# 1_Measurement_and_MPPT.net
KiCad netlist of a schematic drawn in Altium Designer
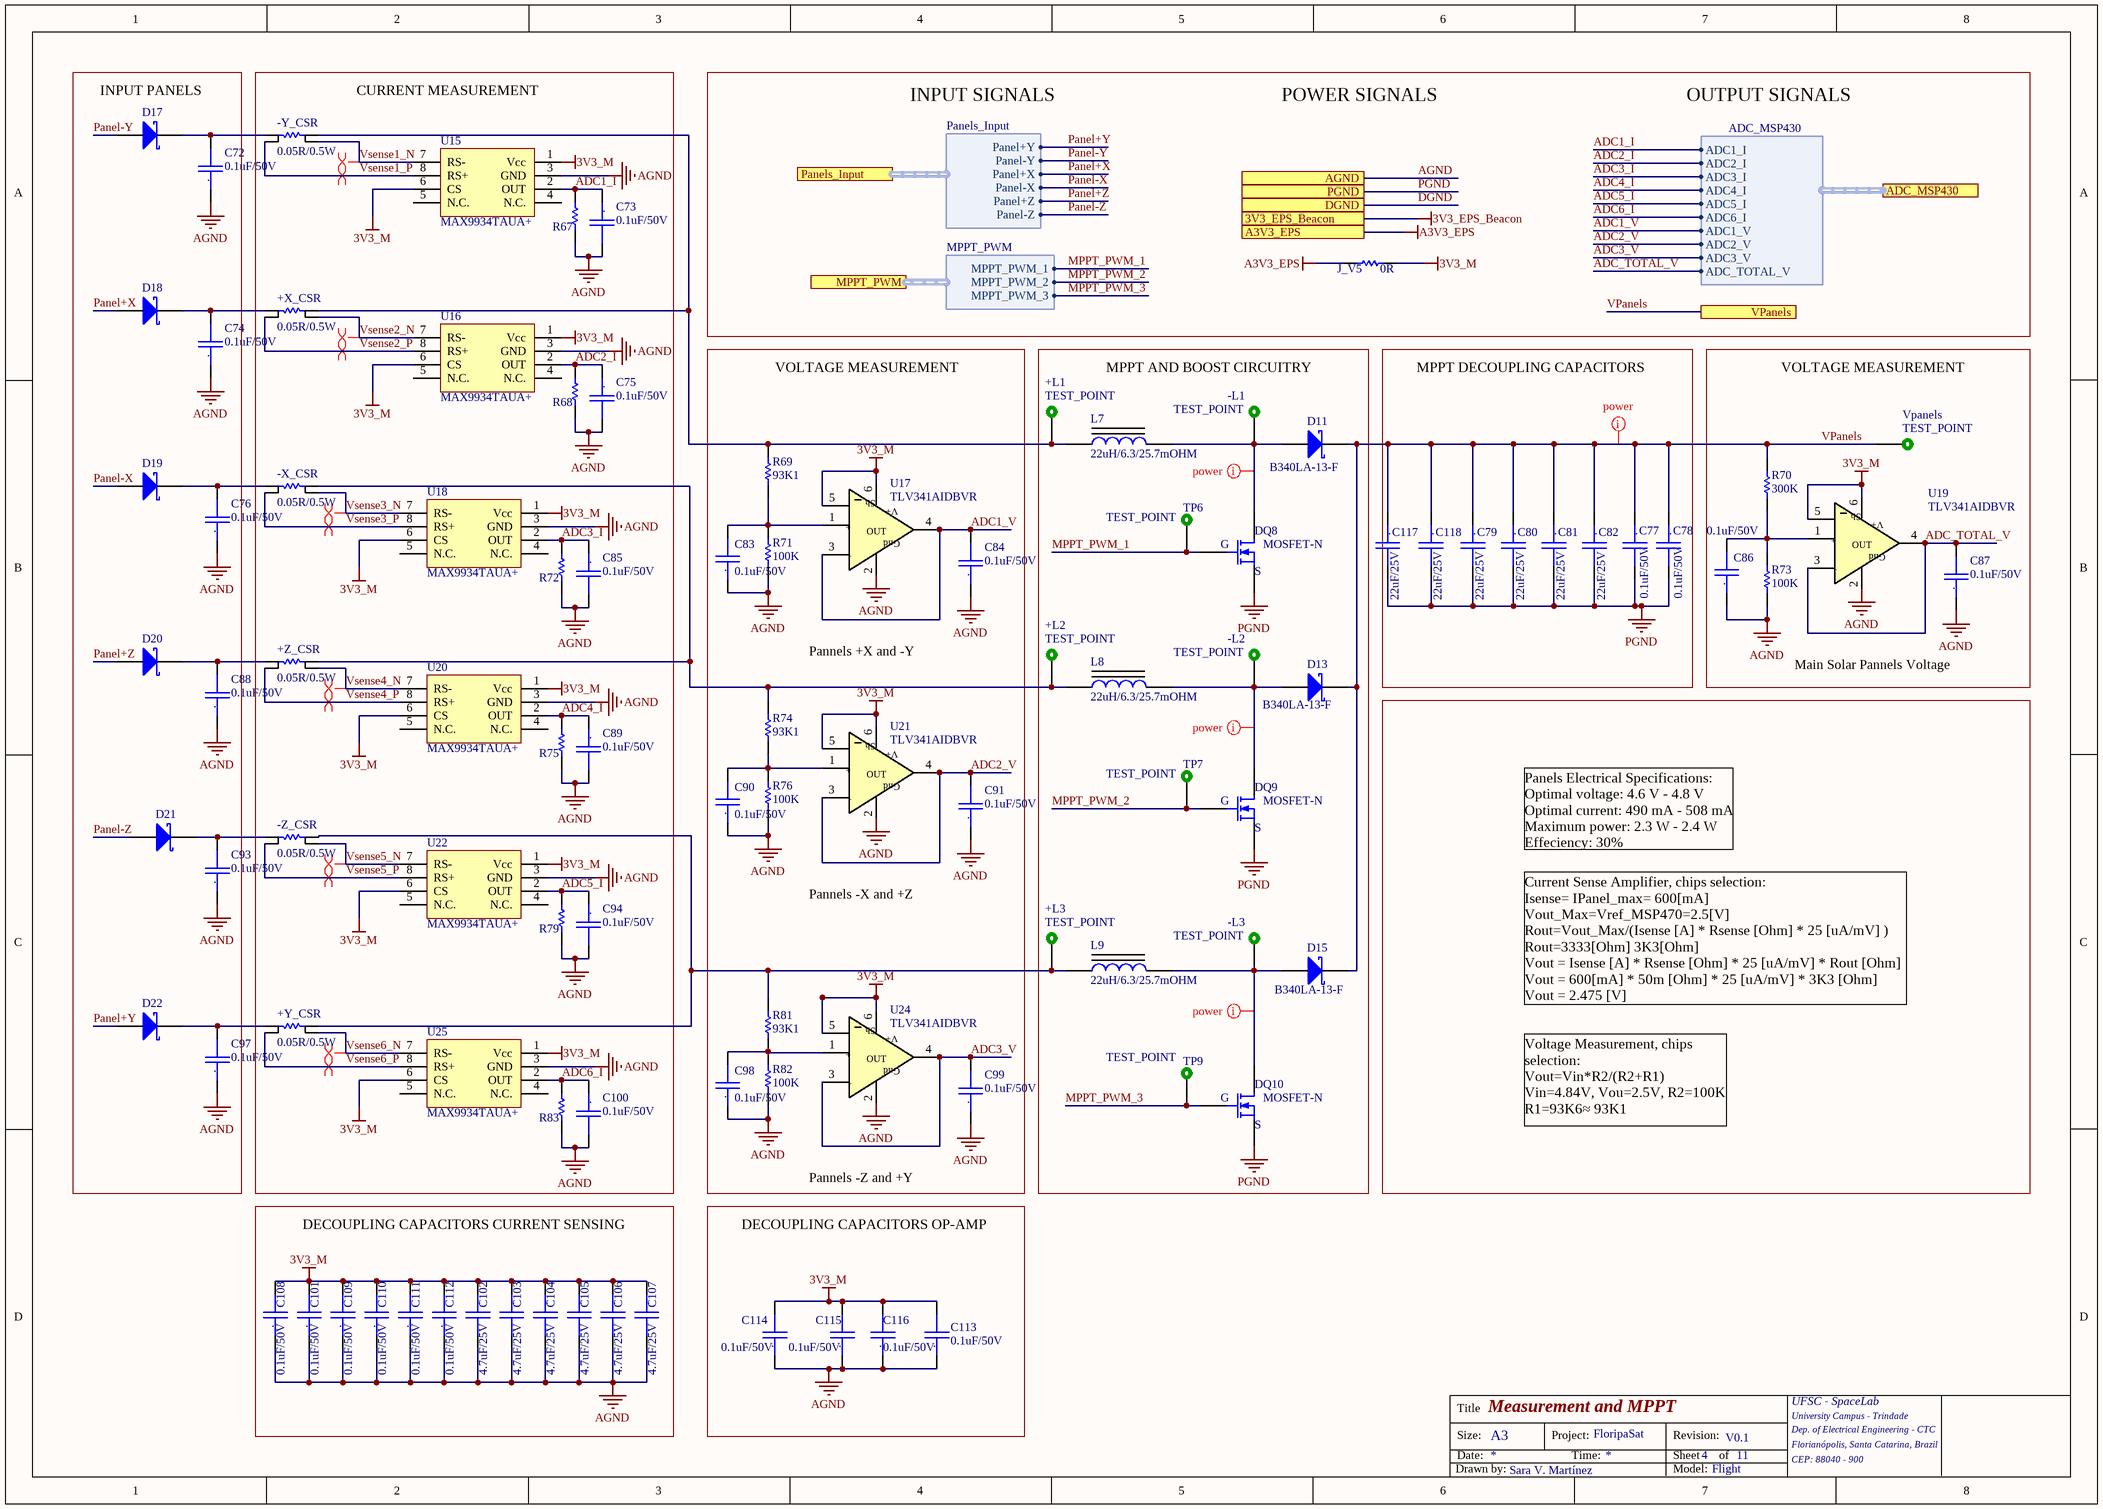
[diagram p0: 1_Measurement_and_MPPT.SchDoc]

(export (version "E")
  (design (tool "Eeschema 10.0.6"))
  (components
    (comp (ref "+L1")
      (value "TEST_POINT")
      (footprint "TEST_POINT")
      (description "Test point")
      (libsource (lib "PCB_Project_FlightModel_EPS") (part "TEST_POINT"))
    )
    (comp (ref "+L2")
      (value "TEST_POINT")
      (footprint "TEST_POINT")
      (description "Test point")
      (libsource (lib "PCB_Project_FlightModel_EPS") (part "TEST_POINT"))
    )
    (comp (ref "+L3")
      (value "TEST_POINT")
      (footprint "TEST_POINT")
      (description "Test point")
      (libsource (lib "PCB_Project_FlightModel_EPS") (part "TEST_POINT"))
    )
    (comp (ref "+X_CSR")
      (value "0.05R/0.5W")
      (footprint "1206 - ohmite")
      (description "Current Sense Resistors - SMD 0.05ohm .5% 4 Terminal")
      (fields (field (name "PARTNUMBER") "LVK12R050DER") (field (name "MANUFACTURER") "Ohmite"))
      (libsource (lib "PCB_Project_FlightModel_EPS") (part "R0.05R_0.5%_0.5W_1206"))
    )
    (comp (ref "+Y_CSR")
      (value "0.05R/0.5W")
      (footprint "1206 - ohmite")
      (description "Current Sense Resistors - SMD 0.05ohm .5% 4 Terminal")
      (fields (field (name "PARTNUMBER") "LVK12R050DER") (field (name "MANUFACTURER") "Ohmite"))
      (libsource (lib "PCB_Project_FlightModel_EPS") (part "R0.05R_0.5%_0.5W_1206"))
    )
    (comp (ref "+Z_CSR")
      (value "0.05R/0.5W")
      (footprint "1206 - ohmite")
      (description "Current Sense Resistors - SMD 0.05ohm .5% 4 Terminal")
      (fields (field (name "PARTNUMBER") "LVK12R050DER") (field (name "MANUFACTURER") "Ohmite"))
      (libsource (lib "PCB_Project_FlightModel_EPS") (part "R0.05R_0.5%_0.5W_1206"))
    )
    (comp (ref "-L1")
      (value "TEST_POINT")
      (footprint "TEST_POINT")
      (description "Test point")
      (libsource (lib "PCB_Project_FlightModel_EPS") (part "TEST_POINT"))
    )
    (comp (ref "-L2")
      (value "TEST_POINT")
      (footprint "TEST_POINT")
      (description "Test point")
      (libsource (lib "PCB_Project_FlightModel_EPS") (part "TEST_POINT"))
    )
    (comp (ref "-L3")
      (value "TEST_POINT")
      (footprint "TEST_POINT")
      (description "Test point")
      (libsource (lib "PCB_Project_FlightModel_EPS") (part "TEST_POINT"))
    )
    (comp (ref "-X_CSR")
      (value "0.05R/0.5W")
      (footprint "1206 - ohmite")
      (description "Current Sense Resistors - SMD 0.05ohm .5% 4 Terminal")
      (fields (field (name "PARTNUMBER") "LVK12R050DER") (field (name "MANUFACTURER") "Ohmite"))
      (libsource (lib "PCB_Project_FlightModel_EPS") (part "R0.05R_0.5%_0.5W_1206"))
    )
    (comp (ref "-Y_CSR")
      (value "0.05R/0.5W")
      (footprint "1206 - ohmite")
      (description "Current Sense Resistors - SMD 0.05ohm .5% 4 Terminal")
      (fields (field (name "PARTNUMBER") "LVK12R050DER") (field (name "MANUFACTURER") "Ohmite"))
      (libsource (lib "PCB_Project_FlightModel_EPS") (part "R0.05R_0.5%_0.5W_1206"))
    )
    (comp (ref "-Z_CSR")
      (value "0.05R/0.5W")
      (footprint "1206 - ohmite")
      (description "Current Sense Resistors - SMD 0.05ohm .5% 4 Terminal")
      (fields (field (name "PARTNUMBER") "LVK12R050DER") (field (name "MANUFACTURER") "Ohmite"))
      (libsource (lib "PCB_Project_FlightModel_EPS") (part "R0.05R_0.5%_0.5W_1206"))
    )
    (comp (ref "C72")
      (value "0.1uF/50V")
      (footprint "CC0603")
      (description "CAP CER 0.1UF 50V 10% X7R 0603")
      (fields (field (name "PARTNUMBER") "CC0603KPX7R9BB104") (field (name "MANUFACTURER") "Yageo"))
      (libsource (lib "PCB_Project_FlightModel_EPS") (part "Cap_Cer_X7R_0.1uF_50V_0603"))
    )
    (comp (ref "C73")
      (value "0.1uF/50V")
      (footprint "CC0603")
      (description "CAP CER 0.1UF 50V 10% X7R 0603")
      (fields (field (name "PARTNUMBER") "CC0603KPX7R9BB104") (field (name "MANUFACTURER") "Yageo"))
      (libsource (lib "PCB_Project_FlightModel_EPS") (part "Cap_Cer_X7R_0.1uF_50V_0603"))
    )
    (comp (ref "C74")
      (value "0.1uF/50V")
      (footprint "CC0603")
      (description "CAP CER 0.1UF 50V 10% X7R 0603")
      (fields (field (name "PARTNUMBER") "CC0603KPX7R9BB104") (field (name "MANUFACTURER") "Yageo"))
      (libsource (lib "PCB_Project_FlightModel_EPS") (part "Cap_Cer_X7R_0.1uF_50V_0603"))
    )
    (comp (ref "C75")
      (value "0.1uF/50V")
      (footprint "CC0603")
      (description "CAP CER 0.1UF 50V 10% X7R 0603")
      (fields (field (name "PARTNUMBER") "CC0603KPX7R9BB104") (field (name "MANUFACTURER") "Yageo"))
      (libsource (lib "PCB_Project_FlightModel_EPS") (part "Cap_Cer_X7R_0.1uF_50V_0603"))
    )
    (comp (ref "C76")
      (value "0.1uF/50V")
      (footprint "CC0603")
      (description "CAP CER 0.1UF 50V 10% X7R 0603")
      (fields (field (name "PARTNUMBER") "CC0603KPX7R9BB104") (field (name "MANUFACTURER") "Yageo"))
      (libsource (lib "PCB_Project_FlightModel_EPS") (part "Cap_Cer_X7R_0.1uF_50V_0603"))
    )
    (comp (ref "C77")
      (value "0.1uF/50V")
      (footprint "CC0805")
      (description "CAP CER 0.1UF 50V 10% X7R 0805")
      (fields (field (name "PARTNUMBER") "CC0805KRX7R9BB104") (field (name "MANUFACTURER") "Yageo"))
      (libsource (lib "PCB_Project_FlightModel_EPS") (part "Cap_Cer_X7R_0.1uF_50V_0805"))
    )
    (comp (ref "C78")
      (value "0.1uF/50V")
      (footprint "CC0805")
      (description "CAP CER 0.1UF 50V 10% X7R 0805")
      (fields (field (name "PARTNUMBER") "CC0805KRX7R9BB104") (field (name "MANUFACTURER") "Yageo"))
      (libsource (lib "PCB_Project_FlightModel_EPS") (part "Cap_Cer_X7R_0.1uF_50V_0805"))
    )
    (comp (ref "C79")
      (value "22uF/25V")
      (footprint "CC1210")
      (description "CAP CER 22uF 25V 10% X7R 1210")
      (fields (field (name "PARTNUMBER") "GRM32ER71E226KE15L") (field (name "MANUFACTURER") "Murata"))
      (libsource (lib "PCB_Project_FlightModel_EPS") (part "Cap_Cer_X7R_22uF_25V_1210"))
    )
    (comp (ref "C80")
      (value "22uF/25V")
      (footprint "CC1210")
      (description "CAP CER 22uF 25V 10% X7R 1210")
      (fields (field (name "PARTNUMBER") "GRM32ER71E226KE15L") (field (name "MANUFACTURER") "Murata"))
      (libsource (lib "PCB_Project_FlightModel_EPS") (part "Cap_Cer_X7R_22uF_25V_1210"))
    )
    (comp (ref "C81")
      (value "22uF/25V")
      (footprint "CC1210")
      (description "CAP CER 22uF 25V 10% X7R 1210")
      (fields (field (name "PARTNUMBER") "GRM32ER71E226KE15L") (field (name "MANUFACTURER") "Murata"))
      (libsource (lib "PCB_Project_FlightModel_EPS") (part "Cap_Cer_X7R_22uF_25V_1210"))
    )
    (comp (ref "C82")
      (value "22uF/25V")
      (footprint "CC1210")
      (description "CAP CER 22uF 25V 10% X7R 1210")
      (fields (field (name "PARTNUMBER") "GRM32ER71E226KE15L") (field (name "MANUFACTURER") "Murata"))
      (libsource (lib "PCB_Project_FlightModel_EPS") (part "Cap_Cer_X7R_22uF_25V_1210"))
    )
    (comp (ref "C83")
      (value "0.1uF/50V")
      (footprint "CC0603")
      (description "CAP CER 0.1UF 50V 10% X7R 0603")
      (fields (field (name "PARTNUMBER") "CC0603KPX7R9BB104") (field (name "MANUFACTURER") "Yageo"))
      (libsource (lib "PCB_Project_FlightModel_EPS") (part "Cap_Cer_X7R_0.1uF_50V_0603"))
    )
    (comp (ref "C84")
      (value "0.1uF/50V")
      (footprint "CC0603")
      (description "CAP CER 0.1UF 50V 10% X7R 0603")
      (fields (field (name "PARTNUMBER") "CC0603KPX7R9BB104") (field (name "MANUFACTURER") "Yageo"))
      (libsource (lib "PCB_Project_FlightModel_EPS") (part "Cap_Cer_X7R_0.1uF_50V_0603"))
    )
    (comp (ref "C85")
      (value "0.1uF/50V")
      (footprint "CC0603")
      (description "CAP CER 0.1UF 50V 10% X7R 0603")
      (fields (field (name "PARTNUMBER") "CC0603KPX7R9BB104") (field (name "MANUFACTURER") "Yageo"))
      (libsource (lib "PCB_Project_FlightModel_EPS") (part "Cap_Cer_X7R_0.1uF_50V_0603"))
    )
    (comp (ref "C86")
      (value "0.1uF/50V")
      (footprint "CC0603")
      (description "CAP CER 0.1UF 50V 10% X7R 0603")
      (fields (field (name "PARTNUMBER") "CC0603KPX7R9BB104") (field (name "MANUFACTURER") "Yageo"))
      (libsource (lib "PCB_Project_FlightModel_EPS") (part "Cap_Cer_X7R_0.1uF_50V_0603"))
    )
    (comp (ref "C87")
      (value "0.1uF/50V")
      (footprint "CC0603")
      (description "CAP CER 0.1UF 50V 10% X7R 0603")
      (fields (field (name "PARTNUMBER") "CC0603KPX7R9BB104") (field (name "MANUFACTURER") "Yageo"))
      (libsource (lib "PCB_Project_FlightModel_EPS") (part "Cap_Cer_X7R_0.1uF_50V_0603"))
    )
    (comp (ref "C88")
      (value "0.1uF/50V")
      (footprint "CC0603")
      (description "CAP CER 0.1UF 50V 10% X7R 0603")
      (fields (field (name "PARTNUMBER") "CC0603KPX7R9BB104") (field (name "MANUFACTURER") "Yageo"))
      (libsource (lib "PCB_Project_FlightModel_EPS") (part "Cap_Cer_X7R_0.1uF_50V_0603"))
    )
    (comp (ref "C89")
      (value "0.1uF/50V")
      (footprint "CC0603")
      (description "CAP CER 0.1UF 50V 10% X7R 0603")
      (fields (field (name "PARTNUMBER") "CC0603KPX7R9BB104") (field (name "MANUFACTURER") "Yageo"))
      (libsource (lib "PCB_Project_FlightModel_EPS") (part "Cap_Cer_X7R_0.1uF_50V_0603"))
    )
    (comp (ref "C90")
      (value "0.1uF/50V")
      (footprint "CC0603")
      (description "CAP CER 0.1UF 50V 10% X7R 0603")
      (fields (field (name "PARTNUMBER") "CC0603KPX7R9BB104") (field (name "MANUFACTURER") "Yageo"))
      (libsource (lib "PCB_Project_FlightModel_EPS") (part "Cap_Cer_X7R_0.1uF_50V_0603"))
    )
    (comp (ref "C91")
      (value "0.1uF/50V")
      (footprint "CC0603")
      (description "CAP CER 0.1UF 50V 10% X7R 0603")
      (fields (field (name "PARTNUMBER") "CC0603KPX7R9BB104") (field (name "MANUFACTURER") "Yageo"))
      (libsource (lib "PCB_Project_FlightModel_EPS") (part "Cap_Cer_X7R_0.1uF_50V_0603"))
    )
    (comp (ref "C93")
      (value "0.1uF/50V")
      (footprint "CC0603")
      (description "CAP CER 0.1UF 50V 10% X7R 0603")
      (fields (field (name "PARTNUMBER") "CC0603KPX7R9BB104") (field (name "MANUFACTURER") "Yageo"))
      (libsource (lib "PCB_Project_FlightModel_EPS") (part "Cap_Cer_X7R_0.1uF_50V_0603"))
    )
    (comp (ref "C94")
      (value "0.1uF/50V")
      (footprint "CC0603")
      (description "CAP CER 0.1UF 50V 10% X7R 0603")
      (fields (field (name "PARTNUMBER") "CC0603KPX7R9BB104") (field (name "MANUFACTURER") "Yageo"))
      (libsource (lib "PCB_Project_FlightModel_EPS") (part "Cap_Cer_X7R_0.1uF_50V_0603"))
    )
    (comp (ref "C97")
      (value "0.1uF/50V")
      (footprint "CC0603")
      (description "CAP CER 0.1UF 50V 10% X7R 0603")
      (fields (field (name "PARTNUMBER") "CC0603KPX7R9BB104") (field (name "MANUFACTURER") "Yageo"))
      (libsource (lib "PCB_Project_FlightModel_EPS") (part "Cap_Cer_X7R_0.1uF_50V_0603"))
    )
    (comp (ref "C98")
      (value "0.1uF/50V")
      (footprint "CC0603")
      (description "CAP CER 0.1UF 50V 10% X7R 0603")
      (fields (field (name "PARTNUMBER") "CC0603KPX7R9BB104") (field (name "MANUFACTURER") "Yageo"))
      (libsource (lib "PCB_Project_FlightModel_EPS") (part "Cap_Cer_X7R_0.1uF_50V_0603"))
    )
    (comp (ref "C99")
      (value "0.1uF/50V")
      (footprint "CC0603")
      (description "CAP CER 0.1UF 50V 10% X7R 0603")
      (fields (field (name "PARTNUMBER") "CC0603KPX7R9BB104") (field (name "MANUFACTURER") "Yageo"))
      (libsource (lib "PCB_Project_FlightModel_EPS") (part "Cap_Cer_X7R_0.1uF_50V_0603"))
    )
    (comp (ref "C100")
      (value "0.1uF/50V")
      (footprint "CC0603")
      (description "CAP CER 0.1UF 50V 10% X7R 0603")
      (fields (field (name "PARTNUMBER") "CC0603KPX7R9BB104") (field (name "MANUFACTURER") "Yageo"))
      (libsource (lib "PCB_Project_FlightModel_EPS") (part "Cap_Cer_X7R_0.1uF_50V_0603"))
    )
    (comp (ref "C101")
      (value "0.1uF/50V")
      (footprint "CC0603")
      (description "CAP CER 0.1UF 50V 10% X7R 0603")
      (fields (field (name "PARTNUMBER") "CC0603KPX7R9BB104") (field (name "MANUFACTURER") "Yageo"))
      (libsource (lib "PCB_Project_FlightModel_EPS") (part "Cap_Cer_X7R_0.1uF_50V_0603"))
    )
    (comp (ref "C102")
      (value "4.7uF/25V")
      (footprint "CC0805")
      (description "CAP CER 4.7uF 25V 10% X7R 0805")
      (fields (field (name "PARTNUMBER") "CC0805KKX7R8BB475") (field (name "MANUFACTURER") "Yageo"))
      (libsource (lib "PCB_Project_FlightModel_EPS") (part "Cap_Cer_X7R_4.7uF_25V_0805"))
    )
    (comp (ref "C103")
      (value "4.7uF/25V")
      (footprint "CC0805")
      (description "CAP CER 4.7uF 25V 10% X7R 0805")
      (fields (field (name "PARTNUMBER") "CC0805KKX7R8BB475") (field (name "MANUFACTURER") "Yageo"))
      (libsource (lib "PCB_Project_FlightModel_EPS") (part "Cap_Cer_X7R_4.7uF_25V_0805"))
    )
    (comp (ref "C104")
      (value "4.7uF/25V")
      (footprint "CC0805")
      (description "CAP CER 4.7uF 25V 10% X7R 0805")
      (fields (field (name "PARTNUMBER") "CC0805KKX7R8BB475") (field (name "MANUFACTURER") "Yageo"))
      (libsource (lib "PCB_Project_FlightModel_EPS") (part "Cap_Cer_X7R_4.7uF_25V_0805"))
    )
    (comp (ref "C105")
      (value "4.7uF/25V")
      (footprint "CC0805")
      (description "CAP CER 4.7uF 25V 10% X7R 0805")
      (fields (field (name "PARTNUMBER") "CC0805KKX7R8BB475") (field (name "MANUFACTURER") "Yageo"))
      (libsource (lib "PCB_Project_FlightModel_EPS") (part "Cap_Cer_X7R_4.7uF_25V_0805"))
    )
    (comp (ref "C106")
      (value "4.7uF/25V")
      (footprint "CC0805")
      (description "CAP CER 4.7uF 25V 10% X7R 0805")
      (fields (field (name "PARTNUMBER") "CC0805KKX7R8BB475") (field (name "MANUFACTURER") "Yageo"))
      (libsource (lib "PCB_Project_FlightModel_EPS") (part "Cap_Cer_X7R_4.7uF_25V_0805"))
    )
    (comp (ref "C107")
      (value "4.7uF/25V")
      (footprint "CC0805")
      (description "CAP CER 4.7uF 25V 10% X7R 0805")
      (fields (field (name "PARTNUMBER") "CC0805KKX7R8BB475") (field (name "MANUFACTURER") "Yageo"))
      (libsource (lib "PCB_Project_FlightModel_EPS") (part "Cap_Cer_X7R_4.7uF_25V_0805"))
    )
    (comp (ref "C108")
      (value "0.1uF/50V")
      (footprint "CC0603")
      (description "CAP CER 0.1UF 50V 10% X7R 0603")
      (fields (field (name "PARTNUMBER") "CC0603KPX7R9BB104") (field (name "MANUFACTURER") "Yageo"))
      (libsource (lib "PCB_Project_FlightModel_EPS") (part "Cap_Cer_X7R_0.1uF_50V_0603"))
    )
    (comp (ref "C109")
      (value "0.1uF/50V")
      (footprint "CC0603")
      (description "CAP CER 0.1UF 50V 10% X7R 0603")
      (fields (field (name "PARTNUMBER") "CC0603KPX7R9BB104") (field (name "MANUFACTURER") "Yageo"))
      (libsource (lib "PCB_Project_FlightModel_EPS") (part "Cap_Cer_X7R_0.1uF_50V_0603"))
    )
    (comp (ref "C110")
      (value "0.1uF/50V")
      (footprint "CC0603")
      (description "CAP CER 0.1UF 50V 10% X7R 0603")
      (fields (field (name "PARTNUMBER") "CC0603KPX7R9BB104") (field (name "MANUFACTURER") "Yageo"))
      (libsource (lib "PCB_Project_FlightModel_EPS") (part "Cap_Cer_X7R_0.1uF_50V_0603"))
    )
    (comp (ref "C111")
      (value "0.1uF/50V")
      (footprint "CC0603")
      (description "CAP CER 0.1UF 50V 10% X7R 0603")
      (fields (field (name "PARTNUMBER") "CC0603KPX7R9BB104") (field (name "MANUFACTURER") "Yageo"))
      (libsource (lib "PCB_Project_FlightModel_EPS") (part "Cap_Cer_X7R_0.1uF_50V_0603"))
    )
    (comp (ref "C112")
      (value "0.1uF/50V")
      (footprint "CC0603")
      (description "CAP CER 0.1UF 50V 10% X7R 0603")
      (fields (field (name "PARTNUMBER") "CC0603KPX7R9BB104") (field (name "MANUFACTURER") "Yageo"))
      (libsource (lib "PCB_Project_FlightModel_EPS") (part "Cap_Cer_X7R_0.1uF_50V_0603"))
    )
    (comp (ref "C113")
      (value "0.1uF/50V")
      (footprint "CC0603")
      (description "CAP CER 0.1UF 50V 10% X7R 0603")
      (fields (field (name "PARTNUMBER") "CC0603KPX7R9BB104") (field (name "MANUFACTURER") "Yageo"))
      (libsource (lib "PCB_Project_FlightModel_EPS") (part "Cap_Cer_X7R_0.1uF_50V_0603"))
    )
    (comp (ref "C114")
      (value "0.1uF/50V")
      (footprint "CC0603")
      (description "CAP CER 0.1UF 50V 10% X7R 0603")
      (fields (field (name "PARTNUMBER") "CC0603KPX7R9BB104") (field (name "MANUFACTURER") "Yageo"))
      (libsource (lib "PCB_Project_FlightModel_EPS") (part "Cap_Cer_X7R_0.1uF_50V_0603"))
    )
    (comp (ref "C115")
      (value "0.1uF/50V")
      (footprint "CC0603")
      (description "CAP CER 0.1UF 50V 10% X7R 0603")
      (fields (field (name "PARTNUMBER") "CC0603KPX7R9BB104") (field (name "MANUFACTURER") "Yageo"))
      (libsource (lib "PCB_Project_FlightModel_EPS") (part "Cap_Cer_X7R_0.1uF_50V_0603"))
    )
    (comp (ref "C116")
      (value "0.1uF/50V")
      (footprint "CC0603")
      (description "CAP CER 0.1UF 50V 10% X7R 0603")
      (fields (field (name "PARTNUMBER") "CC0603KPX7R9BB104") (field (name "MANUFACTURER") "Yageo"))
      (libsource (lib "PCB_Project_FlightModel_EPS") (part "Cap_Cer_X7R_0.1uF_50V_0603"))
    )
    (comp (ref "C117")
      (value "22uF/25V")
      (footprint "CC1210")
      (description "CAP CER 22uF 25V 10% X7R 1210")
      (fields (field (name "PARTNUMBER") "GRM32ER71E226KE15L") (field (name "MANUFACTURER") "Murata"))
      (libsource (lib "PCB_Project_FlightModel_EPS") (part "Cap_Cer_X7R_22uF_25V_1210"))
    )
    (comp (ref "C118")
      (value "22uF/25V")
      (footprint "CC1210")
      (description "CAP CER 22uF 25V 10% X7R 1210")
      (fields (field (name "PARTNUMBER") "GRM32ER71E226KE15L") (field (name "MANUFACTURER") "Murata"))
      (libsource (lib "PCB_Project_FlightModel_EPS") (part "Cap_Cer_X7R_22uF_25V_1210"))
    )
    (comp (ref "D11")
      (value "B340LA-13-F")
      (footprint "DO-214AC")
      (description "DIODE SCHOTTKY 40V 3A B340LA-13-F")
      (fields (field (name "MANUFACTURER") "Diodes"))
      (libsource (lib "PCB_Project_FlightModel_EPS") (part "DIODE_SCHOTTKY_40V_3A_B340LA-13-F"))
    )
    (comp (ref "D13")
      (value "B340LA-13-F")
      (footprint "DO-214AC")
      (description "DIODE SCHOTTKY 40V 3A B340LA-13-F")
      (fields (field (name "MANUFACTURER") "Diodes"))
      (libsource (lib "PCB_Project_FlightModel_EPS") (part "DIODE_SCHOTTKY_40V_3A_B340LA-13-F"))
    )
    (comp (ref "D15")
      (value "B340LA-13-F")
      (footprint "DO-214AC")
      (description "DIODE SCHOTTKY 40V 3A B340LA-13-F")
      (fields (field (name "MANUFACTURER") "Diodes"))
      (libsource (lib "PCB_Project_FlightModel_EPS") (part "DIODE_SCHOTTKY_40V_3A_B340LA-13-F"))
    )
    (comp (ref "D17")
      (value "DNP")
      (footprint "SOD323F")
      (description "DIODE SCHOTTKY 23V 1A SOD323F")
      (fields (field (name "PARTNUMBER") "NSVR0320MW2T1G") (field (name "MANUFACTURER") "ON Semiconductor"))
      (libsource (lib "PCB_Project_FlightModel_EPS") (part "DIODE_SCHOTTKY_23V_1A_NSVR0320MW2T1G"))
    )
    (comp (ref "D18")
      (value "DNP")
      (footprint "SOD323F")
      (description "DIODE SCHOTTKY 23V 1A SOD323F")
      (fields (field (name "PARTNUMBER") "NSVR0320MW2T1G") (field (name "MANUFACTURER") "ON Semiconductor"))
      (libsource (lib "PCB_Project_FlightModel_EPS") (part "DIODE_SCHOTTKY_23V_1A_NSVR0320MW2T1G"))
    )
    (comp (ref "D19")
      (value "DNP")
      (footprint "SOD323F")
      (description "DIODE SCHOTTKY 23V 1A SOD323F")
      (fields (field (name "PARTNUMBER") "NSVR0320MW2T1G") (field (name "MANUFACTURER") "ON Semiconductor"))
      (libsource (lib "PCB_Project_FlightModel_EPS") (part "DIODE_SCHOTTKY_23V_1A_NSVR0320MW2T1G"))
    )
    (comp (ref "D20")
      (value "DNP")
      (footprint "SOD323F")
      (description "DIODE SCHOTTKY 23V 1A SOD323F")
      (fields (field (name "PARTNUMBER") "NSVR0320MW2T1G") (field (name "MANUFACTURER") "ON Semiconductor"))
      (libsource (lib "PCB_Project_FlightModel_EPS") (part "DIODE_SCHOTTKY_23V_1A_NSVR0320MW2T1G"))
    )
    (comp (ref "D21")
      (value "DNP")
      (footprint "SOD323F")
      (description "DIODE SCHOTTKY 23V 1A SOD323F")
      (fields (field (name "PARTNUMBER") "NSVR0320MW2T1G") (field (name "MANUFACTURER") "ON Semiconductor"))
      (libsource (lib "PCB_Project_FlightModel_EPS") (part "DIODE_SCHOTTKY_23V_1A_NSVR0320MW2T1G"))
    )
    (comp (ref "D22")
      (value "DNP")
      (footprint "SOD323F")
      (description "DIODE SCHOTTKY 23V 1A SOD323F")
      (fields (field (name "PARTNUMBER") "NSVR0320MW2T1G") (field (name "MANUFACTURER") "ON Semiconductor"))
      (libsource (lib "PCB_Project_FlightModel_EPS") (part "DIODE_SCHOTTKY_23V_1A_NSVR0320MW2T1G"))
    )
    (comp (ref "J_V5")
      (value "0R")
      (footprint "0805")
      (description "RES 0R OHM 1/8W JUMPER 0805")
      (fields (field (name "PARTNUMBER") "CRCW08050000Z0EA") (field (name "MANUFACTURER") "Vishay"))
      (libsource (lib "PCB_Project_FlightModel_EPS") (part "R0R_JUMPER_1/8W_0805"))
    )
    (comp (ref "L7")
      (value "22uH/6.3/25.7mOHM")
      (footprint "FloripaSatPcbLib:IND_HC9")
      (description "HC9 Series - 22uH / 6.3A / 25.7mOHM")
      (fields (field (name "PARTNUMBER") "HC9-220-R") (field (name "MANUFACTURER") "Eaton Cooper"))
      (libsource (lib "PCB_Project_FlightModel_EPS") (part "IND_POWER_22uH_6.3A_25.7mR"))
    )
    (comp (ref "L8")
      (value "22uH/6.3/25.7mOHM")
      (footprint "FloripaSatPcbLib:IND_HC9")
      (description "HC9 Series - 22uH / 6.3A / 25.7mOHM")
      (fields (field (name "PARTNUMBER") "HC9-220-R") (field (name "MANUFACTURER") "Eaton Cooper"))
      (libsource (lib "PCB_Project_FlightModel_EPS") (part "IND_POWER_22uH_6.3A_25.7mR"))
    )
    (comp (ref "L9")
      (value "22uH/6.3/25.7mOHM")
      (footprint "FloripaSatPcbLib:IND_HC9")
      (description "HC9 Series - 22uH / 6.3A / 25.7mOHM")
      (fields (field (name "PARTNUMBER") "HC9-220-R") (field (name "MANUFACTURER") "Eaton Cooper"))
      (libsource (lib "PCB_Project_FlightModel_EPS") (part "IND_POWER_22uH_6.3A_25.7mR"))
    )
    (comp (ref "Q8")
      (value "MOSFET-N")
      (footprint "SOIC8_Mosfet")
      (description "MOSFET N-Channel 30V Vds 20V Vgs SO-8")
      (fields
        (field (name "PARTNUMBER") "SI4166DY-T1-GE3")
        (field (name "MANUFACTURER") "Vishay Siliconix")
        (field (name "PUBLISHER") "Altium Limited")
      )
      (libsource (lib "PCB_Project_FlightModel_EPS") (part "MOSFET-N_30V_SI4166DY"))
    )
    (comp (ref "Q9")
      (value "MOSFET-N")
      (footprint "SOIC8_Mosfet")
      (description "MOSFET N-Channel 30V Vds 20V Vgs SO-8")
      (fields
        (field (name "PARTNUMBER") "SI4166DY-T1-GE3")
        (field (name "MANUFACTURER") "Vishay Siliconix")
        (field (name "PUBLISHER") "Altium Limited")
      )
      (libsource (lib "PCB_Project_FlightModel_EPS") (part "MOSFET-N_30V_SI4166DY"))
    )
    (comp (ref "Q10")
      (value "MOSFET-N")
      (footprint "SOIC8_Mosfet")
      (description "MOSFET N-Channel 30V Vds 20V Vgs SO-8")
      (fields
        (field (name "PARTNUMBER") "SI4166DY-T1-GE3")
        (field (name "MANUFACTURER") "Vishay Siliconix")
        (field (name "PUBLISHER") "Altium Limited")
      )
      (libsource (lib "PCB_Project_FlightModel_EPS") (part "MOSFET-N_30V_SI4166DY"))
    )
    (comp (ref "R67")
      (value "3k3")
      (footprint "0805")
      (description "RES SMD 3.3K OHM 0.1% 1/10W 0805")
      (fields (field (name "MANUFACTURER") "TE Connectivity Neohm") (field (name "TOLERANCE") "0.1%"))
      (libsource (lib "PCB_Project_FlightModel_EPS") (part "R3.3k_0.1%_1/10W_0805"))
    )
    (comp (ref "R68")
      (value "3k3")
      (footprint "0805")
      (description "RES SMD 3.3K OHM 0.1% 1/10W 0805")
      (fields (field (name "MANUFACTURER") "TE Connectivity Neohm") (field (name "TOLERANCE") "0.1%"))
      (libsource (lib "PCB_Project_FlightModel_EPS") (part "R3.3k_0.1%_1/10W_0805"))
    )
    (comp (ref "R69")
      (value "93K1")
      (footprint "0603")
      (description "RES 93.1K OHM 1/10W 1% 0603")
      (fields (field (name "PARTNUMBER") "CRCW060393K1FKEA") (field (name "MANUFACTURER") "Vishay"))
      (libsource (lib "PCB_Project_FlightModel_EPS") (part "R93.1K_1%_1/10W_0603"))
    )
    (comp (ref "R70")
      (value "300K")
      (footprint "0603")
      (description "RES 300K OHM 1/10W 0.1% 0603")
      (fields (field (name "PARTNUMBER") "RG1608P-304-B-T5") (field (name "MANUFACTURER") "Susumu"))
      (libsource (lib "PCB_Project_FlightModel_EPS") (part "R300K_0.1%_1/10W_0603"))
    )
    (comp (ref "R71")
      (value "100K")
      (footprint "0603")
      (description "RES 100K OHM 1/10W 1% 0603")
      (fields (field (name "PARTNUMBER") "CRCW0603100KFKEA") (field (name "MANUFACTURER") "Vishay"))
      (libsource (lib "PCB_Project_FlightModel_EPS") (part "R100K_1%_1/10W_0603"))
    )
    (comp (ref "R72")
      (value "3k3")
      (footprint "0805")
      (description "RES SMD 3.3K OHM 0.1% 1/10W 0805")
      (fields (field (name "MANUFACTURER") "TE Connectivity Neohm") (field (name "TOLERANCE") "0.1%"))
      (libsource (lib "PCB_Project_FlightModel_EPS") (part "R3.3k_0.1%_1/10W_0805"))
    )
    (comp (ref "R73")
      (value "100K")
      (footprint "0603")
      (description "RES 100K OHM 1/10W 1% 0603")
      (fields (field (name "PARTNUMBER") "CRCW0603100KFKEA") (field (name "MANUFACTURER") "Vishay"))
      (libsource (lib "PCB_Project_FlightModel_EPS") (part "R100K_1%_1/10W_0603"))
    )
    (comp (ref "R74")
      (value "93K1")
      (footprint "0603")
      (description "RES 93.1K OHM 1/10W 1% 0603")
      (fields (field (name "PARTNUMBER") "CRCW060393K1FKEA") (field (name "MANUFACTURER") "Vishay"))
      (libsource (lib "PCB_Project_FlightModel_EPS") (part "R93.1K_1%_1/10W_0603"))
    )
    (comp (ref "R75")
      (value "3k3")
      (footprint "0805")
      (description "RES SMD 3.3K OHM 0.1% 1/10W 0805")
      (fields (field (name "MANUFACTURER") "TE Connectivity Neohm") (field (name "TOLERANCE") "0.1%"))
      (libsource (lib "PCB_Project_FlightModel_EPS") (part "R3.3k_0.1%_1/10W_0805"))
    )
    (comp (ref "R76")
      (value "100K")
      (footprint "0603")
      (description "RES 100K OHM 1/10W 1% 0603")
      (fields (field (name "PARTNUMBER") "CRCW0603100KFKEA") (field (name "MANUFACTURER") "Vishay"))
      (libsource (lib "PCB_Project_FlightModel_EPS") (part "R100K_1%_1/10W_0603"))
    )
    (comp (ref "R79")
      (value "3k3")
      (footprint "0805")
      (description "RES SMD 3.3K OHM 0.1% 1/10W 0805")
      (fields (field (name "MANUFACTURER") "TE Connectivity Neohm") (field (name "TOLERANCE") "0.1%"))
      (libsource (lib "PCB_Project_FlightModel_EPS") (part "R3.3k_0.1%_1/10W_0805"))
    )
    (comp (ref "R81")
      (value "93K1")
      (footprint "0603")
      (description "RES 93.1K OHM 1/10W 1% 0603")
      (fields (field (name "PARTNUMBER") "CRCW060393K1FKEA") (field (name "MANUFACTURER") "Vishay"))
      (libsource (lib "PCB_Project_FlightModel_EPS") (part "R93.1K_1%_1/10W_0603"))
    )
    (comp (ref "R82")
      (value "100K")
      (footprint "0603")
      (description "RES 100K OHM 1/10W 1% 0603")
      (fields (field (name "PARTNUMBER") "CRCW0603100KFKEA") (field (name "MANUFACTURER") "Vishay"))
      (libsource (lib "PCB_Project_FlightModel_EPS") (part "R100K_1%_1/10W_0603"))
    )
    (comp (ref "R83")
      (value "3k3")
      (footprint "0805")
      (description "RES SMD 3.3K OHM 0.1% 1/10W 0805")
      (fields (field (name "MANUFACTURER") "TE Connectivity Neohm") (field (name "TOLERANCE") "0.1%"))
      (libsource (lib "PCB_Project_FlightModel_EPS") (part "R3.3k_0.1%_1/10W_0805"))
    )
    (comp (ref "TP6")
      (value "TEST_POINT")
      (footprint "TEST_POINT")
      (description "Test point")
      (libsource (lib "PCB_Project_FlightModel_EPS") (part "TEST_POINT"))
    )
    (comp (ref "TP7")
      (value "TEST_POINT")
      (footprint "TEST_POINT")
      (description "Test point")
      (libsource (lib "PCB_Project_FlightModel_EPS") (part "TEST_POINT"))
    )
    (comp (ref "TP9")
      (value "TEST_POINT")
      (footprint "TEST_POINT")
      (description "Test point")
      (libsource (lib "PCB_Project_FlightModel_EPS") (part "TEST_POINT"))
    )
    (comp (ref "U15")
      (value "MAX9934TAUA+")
      (footprint "MSOP-8")
      (fields (field (name "MANUFACTURER") "Maxim"))
      (libsource (lib "PCB_Project_FlightModel_EPS") (part "MAX9934TAUA+"))
    )
    (comp (ref "U16")
      (value "MAX9934TAUA+")
      (footprint "MSOP-8")
      (fields (field (name "MANUFACTURER") "Maxim"))
      (libsource (lib "PCB_Project_FlightModel_EPS") (part "MAX9934TAUA+"))
    )
    (comp (ref "U17")
      (value "TLV341AIDBVR")
      (footprint "SOT-23 6L")
      (fields (field (name "MANUFACTURER") "Texas Instruments"))
      (libsource (lib "PCB_Project_FlightModel_EPS") (part "TLV341AIDBVR"))
    )
    (comp (ref "U18")
      (value "MAX9934TAUA+")
      (footprint "MSOP-8")
      (fields (field (name "MANUFACTURER") "Maxim"))
      (libsource (lib "PCB_Project_FlightModel_EPS") (part "MAX9934TAUA+"))
    )
    (comp (ref "U19")
      (value "TLV341AIDBVR")
      (footprint "SOT-23 6L")
      (fields (field (name "MANUFACTURER") "Texas Instruments"))
      (libsource (lib "PCB_Project_FlightModel_EPS") (part "TLV341AIDBVR"))
    )
    (comp (ref "U20")
      (value "MAX9934TAUA+")
      (footprint "MSOP-8")
      (fields (field (name "MANUFACTURER") "Maxim"))
      (libsource (lib "PCB_Project_FlightModel_EPS") (part "MAX9934TAUA+"))
    )
    (comp (ref "U21")
      (value "TLV341AIDBVR")
      (footprint "SOT-23 6L")
      (fields (field (name "MANUFACTURER") "Texas Instruments"))
      (libsource (lib "PCB_Project_FlightModel_EPS") (part "TLV341AIDBVR"))
    )
    (comp (ref "U22")
      (value "MAX9934TAUA+")
      (footprint "MSOP-8")
      (fields (field (name "MANUFACTURER") "Maxim"))
      (libsource (lib "PCB_Project_FlightModel_EPS") (part "MAX9934TAUA+"))
    )
    (comp (ref "U24")
      (value "TLV341AIDBVR")
      (footprint "SOT-23 6L")
      (fields (field (name "MANUFACTURER") "Texas Instruments"))
      (libsource (lib "") (part "TLV341AIDBVR_1"))
    )
    (comp (ref "U25")
      (value "MAX9934TAUA+")
      (footprint "MSOP-8")
      (fields (field (name "MANUFACTURER") "Maxim"))
      (libsource (lib "PCB_Project_FlightModel_EPS") (part "MAX9934TAUA+"))
    )
    (comp (ref "Vpanels")
      (value "TEST_POINT")
      (footprint "TEST_POINT")
      (description "Test point")
      (libsource (lib "PCB_Project_FlightModel_EPS") (part "TEST_POINT"))
    )
  )
  (nets
    (net (code "4") (name "/ADC1_I") (class "Default")
      (node (ref "C73") (pin "1") (pinfunction "1_1") (pintype "passive"))
      (node (ref "R67") (pin "2") (pinfunction "2_2") (pintype "passive"))
      (node (ref "U15") (pin "2") (pinfunction "OUT_2") (pintype "passive"))
    )
    (net (code "5") (name "/ADC1_V") (class "Default")
      (node (ref "C84") (pin "2") (pinfunction "2_2") (pintype "passive"))
      (node (ref "U17") (pin "3") (pinfunction "-IN_3") (pintype "passive"))
      (node (ref "U17") (pin "4") (pinfunction "OUT_4") (pintype "passive"))
    )
    (net (code "6") (name "/ADC2_I") (class "Default")
      (node (ref "C75") (pin "1") (pinfunction "1_1") (pintype "passive"))
      (node (ref "R68") (pin "2") (pinfunction "2_2") (pintype "passive"))
      (node (ref "U16") (pin "2") (pinfunction "OUT_2") (pintype "passive"))
    )
    (net (code "7") (name "/ADC2_V") (class "Default")
      (node (ref "C91") (pin "2") (pinfunction "2_2") (pintype "passive"))
      (node (ref "U21") (pin "3") (pinfunction "-IN_3") (pintype "passive"))
      (node (ref "U21") (pin "4") (pinfunction "OUT_4") (pintype "passive"))
    )
    (net (code "8") (name "/ADC3_I") (class "Default")
      (node (ref "C85") (pin "1") (pinfunction "1_1") (pintype "passive"))
      (node (ref "R72") (pin "2") (pinfunction "2_2") (pintype "passive"))
      (node (ref "U18") (pin "2") (pinfunction "OUT_2") (pintype "passive"))
    )
    (net (code "9") (name "/ADC3_V") (class "Default")
      (node (ref "C99") (pin "2") (pinfunction "2_2") (pintype "passive"))
      (node (ref "U24") (pin "3") (pinfunction "-IN_3") (pintype "passive"))
      (node (ref "U24") (pin "4") (pinfunction "OUT_4") (pintype "passive"))
    )
    (net (code "10") (name "/ADC4_I") (class "Default")
      (node (ref "C89") (pin "1") (pinfunction "1_1") (pintype "passive"))
      (node (ref "R75") (pin "2") (pinfunction "2_2") (pintype "passive"))
      (node (ref "U20") (pin "2") (pinfunction "OUT_2") (pintype "passive"))
    )
    (net (code "11") (name "/ADC5_I") (class "Default")
      (node (ref "C94") (pin "1") (pinfunction "1_1") (pintype "passive"))
      (node (ref "R79") (pin "2") (pinfunction "2_2") (pintype "passive"))
      (node (ref "U22") (pin "2") (pinfunction "OUT_2") (pintype "passive"))
    )
    (net (code "12") (name "/ADC6_I") (class "Default")
      (node (ref "C100") (pin "1") (pinfunction "1_1") (pintype "passive"))
      (node (ref "R83") (pin "2") (pinfunction "2_2") (pintype "passive"))
      (node (ref "U25") (pin "2") (pinfunction "OUT_2") (pintype "passive"))
    )
    (net (code "13") (name "/ADC_TOTAL_V") (class "Default")
      (node (ref "C87") (pin "2") (pinfunction "2_2") (pintype "passive"))
      (node (ref "U19") (pin "3") (pinfunction "-IN_3") (pintype "passive"))
      (node (ref "U19") (pin "4") (pinfunction "OUT_4") (pintype "passive"))
    )
    (net (code "15") (name "/MPPT_PWM_1") (class "Default")
      (node (ref "Q8") (pin "2") (pinfunction "G_2") (pintype "passive"))
      (node (ref "TP6") (pin "1") (pinfunction "1_1") (pintype "passive"))
    )
    (net (code "16") (name "/MPPT_PWM_2") (class "Default")
      (node (ref "Q9") (pin "2") (pinfunction "G_2") (pintype "passive"))
      (node (ref "TP7") (pin "1") (pinfunction "1_1") (pintype "passive"))
    )
    (net (code "17") (name "/MPPT_PWM_3") (class "Default")
      (node (ref "Q10") (pin "2") (pinfunction "G_2") (pintype "passive"))
      (node (ref "TP9") (pin "1") (pinfunction "1_1") (pintype "passive"))
    )
    (net (code "18") (name "/Panel+X") (class "Default")
      (node (ref "D18") (pin "2") (pinfunction "A_2") (pintype "passive"))
    )
    (net (code "19") (name "/Panel+Y") (class "Default")
      (node (ref "D22") (pin "2") (pinfunction "A_2") (pintype "passive"))
    )
    (net (code "20") (name "/Panel+Z") (class "Default")
      (node (ref "D20") (pin "2") (pinfunction "A_2") (pintype "passive"))
    )
    (net (code "21") (name "/Panel-X") (class "Default")
      (node (ref "D19") (pin "2") (pinfunction "A_2") (pintype "passive"))
    )
    (net (code "22") (name "/Panel-Y") (class "Default")
      (node (ref "D17") (pin "2") (pinfunction "A_2") (pintype "passive"))
    )
    (net (code "23") (name "/Panel-Z") (class "Default")
      (node (ref "D21") (pin "2") (pinfunction "A_2") (pintype "passive"))
    )
    (net (code "24") (name "/VPanels") (class "Default")
      (node (ref "C117") (pin "1") (pinfunction "1_1") (pintype "passive"))
      (node (ref "C118") (pin "1") (pinfunction "1_1") (pintype "passive"))
      (node (ref "C77") (pin "1") (pinfunction "1_1") (pintype "passive"))
      (node (ref "C78") (pin "1") (pinfunction "1_1") (pintype "passive"))
      (node (ref "C79") (pin "1") (pinfunction "1_1") (pintype "passive"))
      (node (ref "C80") (pin "1") (pinfunction "1_1") (pintype "passive"))
      (node (ref "C81") (pin "1") (pinfunction "1_1") (pintype "passive"))
      (node (ref "C82") (pin "1") (pinfunction "1_1") (pintype "passive"))
      (node (ref "D11") (pin "1") (pinfunction "K_1") (pintype "passive"))
      (node (ref "D13") (pin "1") (pinfunction "K_1") (pintype "passive"))
      (node (ref "D15") (pin "1") (pinfunction "K_1") (pintype "passive"))
      (node (ref "R70") (pin "2") (pinfunction "2_2") (pintype "passive"))
      (node (ref "Vpanels") (pin "1") (pinfunction "1_1") (pintype "passive"))
    )
    (net (code "25") (name "/Vsense1_N") (class "Default")
      (node (ref "-Y_CSR") (pin "4") (pinfunction "4_4") (pintype "passive"))
      (node (ref "U15") (pin "7") (pinfunction "RS-_7") (pintype "passive"))
    )
    (net (code "26") (name "/Vsense1_P") (class "Default")
      (node (ref "-Y_CSR") (pin "3") (pinfunction "3_3") (pintype "passive"))
      (node (ref "U15") (pin "8") (pinfunction "RS+_8") (pintype "passive"))
    )
    (net (code "27") (name "/Vsense2_N") (class "Default")
      (node (ref "+X_CSR") (pin "4") (pinfunction "4_4") (pintype "passive"))
      (node (ref "U16") (pin "7") (pinfunction "RS-_7") (pintype "passive"))
    )
    (net (code "28") (name "/Vsense2_P") (class "Default")
      (node (ref "+X_CSR") (pin "3") (pinfunction "3_3") (pintype "passive"))
      (node (ref "U16") (pin "8") (pinfunction "RS+_8") (pintype "passive"))
    )
    (net (code "29") (name "/Vsense3_N") (class "Default")
      (node (ref "-X_CSR") (pin "4") (pinfunction "4_4") (pintype "passive"))
      (node (ref "U18") (pin "7") (pinfunction "RS-_7") (pintype "passive"))
    )
    (net (code "30") (name "/Vsense3_P") (class "Default")
      (node (ref "-X_CSR") (pin "3") (pinfunction "3_3") (pintype "passive"))
      (node (ref "U18") (pin "8") (pinfunction "RS+_8") (pintype "passive"))
    )
    (net (code "31") (name "/Vsense4_N") (class "Default")
      (node (ref "+Z_CSR") (pin "4") (pinfunction "4_4") (pintype "passive"))
      (node (ref "U20") (pin "7") (pinfunction "RS-_7") (pintype "passive"))
    )
    (net (code "32") (name "/Vsense4_P") (class "Default")
      (node (ref "+Z_CSR") (pin "3") (pinfunction "3_3") (pintype "passive"))
      (node (ref "U20") (pin "8") (pinfunction "RS+_8") (pintype "passive"))
    )
    (net (code "33") (name "/Vsense5_N") (class "Default")
      (node (ref "-Z_CSR") (pin "4") (pinfunction "4_4") (pintype "passive"))
      (node (ref "U22") (pin "7") (pinfunction "RS-_7") (pintype "passive"))
    )
    (net (code "34") (name "/Vsense5_P") (class "Default")
      (node (ref "-Z_CSR") (pin "3") (pinfunction "3_3") (pintype "passive"))
      (node (ref "U22") (pin "8") (pinfunction "RS+_8") (pintype "passive"))
    )
    (net (code "35") (name "/Vsense6_N") (class "Default")
      (node (ref "+Y_CSR") (pin "4") (pinfunction "4_4") (pintype "passive"))
      (node (ref "U25") (pin "7") (pinfunction "RS-_7") (pintype "passive"))
    )
    (net (code "36") (name "/Vsense6_P") (class "Default")
      (node (ref "+Y_CSR") (pin "3") (pinfunction "3_3") (pintype "passive"))
      (node (ref "U25") (pin "8") (pinfunction "RS+_8") (pintype "passive"))
    )
    (net (code "41") (name "3V3_M") (class "Default")
      (node (ref "C101") (pin "2") (pinfunction "2_2") (pintype "passive"))
      (node (ref "C102") (pin "1") (pinfunction "1_1") (pintype "passive"))
      (node (ref "C103") (pin "1") (pinfunction "1_1") (pintype "passive"))
      (node (ref "C104") (pin "1") (pinfunction "1_1") (pintype "passive"))
      (node (ref "C105") (pin "1") (pinfunction "1_1") (pintype "passive"))
      (node (ref "C106") (pin "1") (pinfunction "1_1") (pintype "passive"))
      (node (ref "C107") (pin "1") (pinfunction "1_1") (pintype "passive"))
      (node (ref "C108") (pin "2") (pinfunction "2_2") (pintype "passive"))
      (node (ref "C109") (pin "2") (pinfunction "2_2") (pintype "passive"))
      (node (ref "C110") (pin "2") (pinfunction "2_2") (pintype "passive"))
      (node (ref "C111") (pin "2") (pinfunction "2_2") (pintype "passive"))
      (node (ref "C112") (pin "2") (pinfunction "2_2") (pintype "passive"))
      (node (ref "C113") (pin "2") (pinfunction "2_2") (pintype "passive"))
      (node (ref "C114") (pin "2") (pinfunction "2_2") (pintype "passive"))
      (node (ref "C115") (pin "2") (pinfunction "2_2") (pintype "passive"))
      (node (ref "C116") (pin "2") (pinfunction "2_2") (pintype "passive"))
      (node (ref "J_V5") (pin "1") (pinfunction "1_1") (pintype "passive"))
      (node (ref "U15") (pin "1") (pinfunction "Vcc_1") (pintype "passive"))
      (node (ref "U15") (pin "6") (pinfunction "CS_6") (pintype "passive"))
      (node (ref "U16") (pin "1") (pinfunction "Vcc_1") (pintype "passive"))
      (node (ref "U16") (pin "6") (pinfunction "CS_6") (pintype "passive"))
      (node (ref "U17") (pin "5") (pinfunction "EN_5") (pintype "passive"))
      (node (ref "U17") (pin "6") (pinfunction "V+_6") (pintype "passive"))
      (node (ref "U18") (pin "1") (pinfunction "Vcc_1") (pintype "passive"))
      (node (ref "U18") (pin "6") (pinfunction "CS_6") (pintype "passive"))
      (node (ref "U19") (pin "5") (pinfunction "EN_5") (pintype "passive"))
      (node (ref "U19") (pin "6") (pinfunction "V+_6") (pintype "passive"))
      (node (ref "U20") (pin "1") (pinfunction "Vcc_1") (pintype "passive"))
      (node (ref "U20") (pin "6") (pinfunction "CS_6") (pintype "passive"))
      (node (ref "U21") (pin "5") (pinfunction "EN_5") (pintype "passive"))
      (node (ref "U21") (pin "6") (pinfunction "V+_6") (pintype "passive"))
      (node (ref "U22") (pin "1") (pinfunction "Vcc_1") (pintype "passive"))
      (node (ref "U22") (pin "6") (pinfunction "CS_6") (pintype "passive"))
      (node (ref "U24") (pin "5") (pinfunction "EN_5") (pintype "passive"))
      (node (ref "U24") (pin "6") (pinfunction "V+_6") (pintype "passive"))
      (node (ref "U25") (pin "1") (pinfunction "Vcc_1") (pintype "passive"))
      (node (ref "U25") (pin "6") (pinfunction "CS_6") (pintype "passive"))
    )
    (net (code "42") (name "A3V3_EPS") (class "Default")
      (node (ref "J_V5") (pin "2") (pinfunction "2_2") (pintype "passive"))
    )
    (net (code "43") (name "AGND") (class "Default")
      (node (ref "C100") (pin "2") (pinfunction "2_2") (pintype "passive"))
      (node (ref "C101") (pin "1") (pinfunction "1_1") (pintype "passive"))
      (node (ref "C102") (pin "2") (pinfunction "2_2") (pintype "passive"))
      (node (ref "C103") (pin "2") (pinfunction "2_2") (pintype "passive"))
      (node (ref "C104") (pin "2") (pinfunction "2_2") (pintype "passive"))
      (node (ref "C105") (pin "2") (pinfunction "2_2") (pintype "passive"))
      (node (ref "C106") (pin "2") (pinfunction "2_2") (pintype "passive"))
      (node (ref "C107") (pin "2") (pinfunction "2_2") (pintype "passive"))
      (node (ref "C108") (pin "1") (pinfunction "1_1") (pintype "passive"))
      (node (ref "C109") (pin "1") (pinfunction "1_1") (pintype "passive"))
      (node (ref "C110") (pin "1") (pinfunction "1_1") (pintype "passive"))
      (node (ref "C111") (pin "1") (pinfunction "1_1") (pintype "passive"))
      (node (ref "C112") (pin "1") (pinfunction "1_1") (pintype "passive"))
      (node (ref "C113") (pin "1") (pinfunction "1_1") (pintype "passive"))
      (node (ref "C114") (pin "1") (pinfunction "1_1") (pintype "passive"))
      (node (ref "C115") (pin "1") (pinfunction "1_1") (pintype "passive"))
      (node (ref "C116") (pin "1") (pinfunction "1_1") (pintype "passive"))
      (node (ref "C72") (pin "1") (pinfunction "1_1") (pintype "passive"))
      (node (ref "C73") (pin "2") (pinfunction "2_2") (pintype "passive"))
      (node (ref "C74") (pin "1") (pinfunction "1_1") (pintype "passive"))
      (node (ref "C75") (pin "2") (pinfunction "2_2") (pintype "passive"))
      (node (ref "C76") (pin "1") (pinfunction "1_1") (pintype "passive"))
      (node (ref "C83") (pin "1") (pinfunction "1_1") (pintype "passive"))
      (node (ref "C84") (pin "1") (pinfunction "1_1") (pintype "passive"))
      (node (ref "C85") (pin "2") (pinfunction "2_2") (pintype "passive"))
      (node (ref "C86") (pin "1") (pinfunction "1_1") (pintype "passive"))
      (node (ref "C87") (pin "1") (pinfunction "1_1") (pintype "passive"))
      (node (ref "C88") (pin "1") (pinfunction "1_1") (pintype "passive"))
      (node (ref "C89") (pin "2") (pinfunction "2_2") (pintype "passive"))
      (node (ref "C90") (pin "1") (pinfunction "1_1") (pintype "passive"))
      (node (ref "C91") (pin "1") (pinfunction "1_1") (pintype "passive"))
      (node (ref "C93") (pin "1") (pinfunction "1_1") (pintype "passive"))
      (node (ref "C94") (pin "2") (pinfunction "2_2") (pintype "passive"))
      (node (ref "C97") (pin "1") (pinfunction "1_1") (pintype "passive"))
      (node (ref "C98") (pin "1") (pinfunction "1_1") (pintype "passive"))
      (node (ref "C99") (pin "1") (pinfunction "1_1") (pintype "passive"))
      (node (ref "R67") (pin "1") (pinfunction "1_1") (pintype "passive"))
      (node (ref "R68") (pin "1") (pinfunction "1_1") (pintype "passive"))
      (node (ref "R71") (pin "1") (pinfunction "1_1") (pintype "passive"))
      (node (ref "R72") (pin "1") (pinfunction "1_1") (pintype "passive"))
      (node (ref "R73") (pin "1") (pinfunction "1_1") (pintype "passive"))
      (node (ref "R75") (pin "1") (pinfunction "1_1") (pintype "passive"))
      (node (ref "R76") (pin "1") (pinfunction "1_1") (pintype "passive"))
      (node (ref "R79") (pin "1") (pinfunction "1_1") (pintype "passive"))
      (node (ref "R82") (pin "1") (pinfunction "1_1") (pintype "passive"))
      (node (ref "R83") (pin "1") (pinfunction "1_1") (pintype "passive"))
      (node (ref "U15") (pin "3") (pinfunction "GND_3") (pintype "passive"))
      (node (ref "U16") (pin "3") (pinfunction "GND_3") (pintype "passive"))
      (node (ref "U17") (pin "2") (pinfunction "Gnd_2") (pintype "passive"))
      (node (ref "U18") (pin "3") (pinfunction "GND_3") (pintype "passive"))
      (node (ref "U19") (pin "2") (pinfunction "Gnd_2") (pintype "passive"))
      (node (ref "U20") (pin "3") (pinfunction "GND_3") (pintype "passive"))
      (node (ref "U21") (pin "2") (pinfunction "Gnd_2") (pintype "passive"))
      (node (ref "U22") (pin "3") (pinfunction "GND_3") (pintype "passive"))
      (node (ref "U24") (pin "2") (pinfunction "Gnd_2") (pintype "passive"))
      (node (ref "U25") (pin "3") (pinfunction "GND_3") (pintype "passive"))
    )
    (net (code "44") (name "Net-(+L1-Pad1)") (class "Default")
      (node (ref "+L1") (pin "1") (pinfunction "1_1") (pintype "passive"))
      (node (ref "+X_CSR") (pin "2") (pinfunction "2_2") (pintype "passive"))
      (node (ref "-Y_CSR") (pin "2") (pinfunction "2_2") (pintype "passive"))
      (node (ref "L7") (pin "1") (pinfunction "1_1") (pintype "passive"))
      (node (ref "R69") (pin "2") (pinfunction "2_2") (pintype "passive"))
    )
    (net (code "45") (name "Net-(+L2-Pad1)") (class "Default")
      (node (ref "+L2") (pin "1") (pinfunction "1_1") (pintype "passive"))
      (node (ref "+Z_CSR") (pin "2") (pinfunction "2_2") (pintype "passive"))
      (node (ref "-X_CSR") (pin "2") (pinfunction "2_2") (pintype "passive"))
      (node (ref "L8") (pin "1") (pinfunction "1_1") (pintype "passive"))
      (node (ref "R74") (pin "2") (pinfunction "2_2") (pintype "passive"))
    )
    (net (code "46") (name "Net-(+L3-Pad1)") (class "Default")
      (node (ref "+L3") (pin "1") (pinfunction "1_1") (pintype "passive"))
      (node (ref "+Y_CSR") (pin "2") (pinfunction "2_2") (pintype "passive"))
      (node (ref "-Z_CSR") (pin "2") (pinfunction "2_2") (pintype "passive"))
      (node (ref "L9") (pin "1") (pinfunction "1_1") (pintype "passive"))
      (node (ref "R81") (pin "2") (pinfunction "2_2") (pintype "passive"))
    )
    (net (code "47") (name "Net-(D11-A)") (class "Default")
      (node (ref "-L1") (pin "1") (pinfunction "1_1") (pintype "passive"))
      (node (ref "D11") (pin "2") (pinfunction "A_2") (pintype "passive"))
      (node (ref "L7") (pin "2") (pinfunction "2_2") (pintype "passive"))
      (node (ref "Q8") (pin "3") (pinfunction "D_3") (pintype "passive"))
    )
    (net (code "48") (name "Net-(D13-A)") (class "Default")
      (node (ref "-L2") (pin "1") (pinfunction "1_1") (pintype "passive"))
      (node (ref "D13") (pin "2") (pinfunction "A_2") (pintype "passive"))
      (node (ref "L8") (pin "2") (pinfunction "2_2") (pintype "passive"))
      (node (ref "Q9") (pin "3") (pinfunction "D_3") (pintype "passive"))
    )
    (net (code "49") (name "Net-(D15-A)") (class "Default")
      (node (ref "-L3") (pin "1") (pinfunction "1_1") (pintype "passive"))
      (node (ref "D15") (pin "2") (pinfunction "A_2") (pintype "passive"))
      (node (ref "L9") (pin "2") (pinfunction "2_2") (pintype "passive"))
      (node (ref "Q10") (pin "3") (pinfunction "D_3") (pintype "passive"))
    )
    (net (code "50") (name "Net-(D17-K)") (class "Default")
      (node (ref "-Y_CSR") (pin "1") (pinfunction "1_1") (pintype "passive"))
      (node (ref "C72") (pin "2") (pinfunction "2_2") (pintype "passive"))
      (node (ref "D17") (pin "1") (pinfunction "K_1") (pintype "passive"))
    )
    (net (code "51") (name "Net-(D18-K)") (class "Default")
      (node (ref "+X_CSR") (pin "1") (pinfunction "1_1") (pintype "passive"))
      (node (ref "C74") (pin "2") (pinfunction "2_2") (pintype "passive"))
      (node (ref "D18") (pin "1") (pinfunction "K_1") (pintype "passive"))
    )
    (net (code "52") (name "Net-(D19-K)") (class "Default")
      (node (ref "-X_CSR") (pin "1") (pinfunction "1_1") (pintype "passive"))
      (node (ref "C76") (pin "2") (pinfunction "2_2") (pintype "passive"))
      (node (ref "D19") (pin "1") (pinfunction "K_1") (pintype "passive"))
    )
    (net (code "53") (name "Net-(D20-K)") (class "Default")
      (node (ref "+Z_CSR") (pin "1") (pinfunction "1_1") (pintype "passive"))
      (node (ref "C88") (pin "2") (pinfunction "2_2") (pintype "passive"))
      (node (ref "D20") (pin "1") (pinfunction "K_1") (pintype "passive"))
    )
    (net (code "54") (name "Net-(D21-K)") (class "Default")
      (node (ref "-Z_CSR") (pin "1") (pinfunction "1_1") (pintype "passive"))
      (node (ref "C93") (pin "2") (pinfunction "2_2") (pintype "passive"))
      (node (ref "D21") (pin "1") (pinfunction "K_1") (pintype "passive"))
    )
    (net (code "55") (name "Net-(D22-K)") (class "Default")
      (node (ref "+Y_CSR") (pin "1") (pinfunction "1_1") (pintype "passive"))
      (node (ref "C97") (pin "2") (pinfunction "2_2") (pintype "passive"))
      (node (ref "D22") (pin "1") (pinfunction "K_1") (pintype "passive"))
    )
    (net (code "56") (name "Net-(U17-+IN)") (class "Default")
      (node (ref "C83") (pin "2") (pinfunction "2_2") (pintype "passive"))
      (node (ref "R69") (pin "1") (pinfunction "1_1") (pintype "passive"))
      (node (ref "R71") (pin "2") (pinfunction "2_2") (pintype "passive"))
      (node (ref "U17") (pin "1") (pinfunction "+IN_1") (pintype "passive"))
    )
    (net (code "57") (name "Net-(U19-+IN)") (class "Default")
      (node (ref "C86") (pin "2") (pinfunction "2_2") (pintype "passive"))
      (node (ref "R70") (pin "1") (pinfunction "1_1") (pintype "passive"))
      (node (ref "R73") (pin "2") (pinfunction "2_2") (pintype "passive"))
      (node (ref "U19") (pin "1") (pinfunction "+IN_1") (pintype "passive"))
    )
    (net (code "58") (name "Net-(U21-+IN)") (class "Default")
      (node (ref "C90") (pin "2") (pinfunction "2_2") (pintype "passive"))
      (node (ref "R74") (pin "1") (pinfunction "1_1") (pintype "passive"))
      (node (ref "R76") (pin "2") (pinfunction "2_2") (pintype "passive"))
      (node (ref "U21") (pin "1") (pinfunction "+IN_1") (pintype "passive"))
    )
    (net (code "59") (name "Net-(U24-+IN)") (class "Default")
      (node (ref "C98") (pin "2") (pinfunction "2_2") (pintype "passive"))
      (node (ref "R81") (pin "1") (pinfunction "1_1") (pintype "passive"))
      (node (ref "R82") (pin "2") (pinfunction "2_2") (pintype "passive"))
      (node (ref "U24") (pin "1") (pinfunction "+IN_1") (pintype "passive"))
    )
    (net (code "60") (name "PGND") (class "Default")
      (node (ref "C117") (pin "2") (pinfunction "2_2") (pintype "passive"))
      (node (ref "C118") (pin "2") (pinfunction "2_2") (pintype "passive"))
      (node (ref "C77") (pin "2") (pinfunction "2_2") (pintype "passive"))
      (node (ref "C78") (pin "2") (pinfunction "2_2") (pintype "passive"))
      (node (ref "C79") (pin "2") (pinfunction "2_2") (pintype "passive"))
      (node (ref "C80") (pin "2") (pinfunction "2_2") (pintype "passive"))
      (node (ref "C81") (pin "2") (pinfunction "2_2") (pintype "passive"))
      (node (ref "C82") (pin "2") (pinfunction "2_2") (pintype "passive"))
      (node (ref "Q10") (pin "1") (pinfunction "S_1") (pintype "passive"))
      (node (ref "Q8") (pin "1") (pinfunction "S_1") (pintype "passive"))
      (node (ref "Q9") (pin "1") (pinfunction "S_1") (pintype "passive"))
    )
    (net (code "61") (name "unconnected-(U15-N.C.-Pad4)") (class "Default")
      (node (ref "U15") (pin "4") (pinfunction "N.C._4") (pintype "passive"))
    )
    (net (code "62") (name "unconnected-(U15-N.C.-Pad5)") (class "Default")
      (node (ref "U15") (pin "5") (pinfunction "N.C._5") (pintype "passive"))
    )
    (net (code "63") (name "unconnected-(U16-N.C.-Pad4)") (class "Default")
      (node (ref "U16") (pin "4") (pinfunction "N.C._4") (pintype "passive"))
    )
    (net (code "64") (name "unconnected-(U16-N.C.-Pad5)") (class "Default")
      (node (ref "U16") (pin "5") (pinfunction "N.C._5") (pintype "passive"))
    )
    (net (code "65") (name "unconnected-(U18-N.C.-Pad4)") (class "Default")
      (node (ref "U18") (pin "4") (pinfunction "N.C._4") (pintype "passive"))
    )
    (net (code "66") (name "unconnected-(U18-N.C.-Pad5)") (class "Default")
      (node (ref "U18") (pin "5") (pinfunction "N.C._5") (pintype "passive"))
    )
    (net (code "67") (name "unconnected-(U20-N.C.-Pad4)") (class "Default")
      (node (ref "U20") (pin "4") (pinfunction "N.C._4") (pintype "passive"))
    )
    (net (code "68") (name "unconnected-(U20-N.C.-Pad5)") (class "Default")
      (node (ref "U20") (pin "5") (pinfunction "N.C._5") (pintype "passive"))
    )
    (net (code "69") (name "unconnected-(U22-N.C.-Pad4)") (class "Default")
      (node (ref "U22") (pin "4") (pinfunction "N.C._4") (pintype "passive"))
    )
    (net (code "70") (name "unconnected-(U22-N.C.-Pad5)") (class "Default")
      (node (ref "U22") (pin "5") (pinfunction "N.C._5") (pintype "passive"))
    )
    (net (code "71") (name "unconnected-(U25-N.C.-Pad4)") (class "Default")
      (node (ref "U25") (pin "4") (pinfunction "N.C._4") (pintype "passive"))
    )
    (net (code "72") (name "unconnected-(U25-N.C.-Pad5)") (class "Default")
      (node (ref "U25") (pin "5") (pinfunction "N.C._5") (pintype "passive"))
    )
  )
)
